# R2020Interface.net
KiCad netlist of a schematic drawn in EAGLE
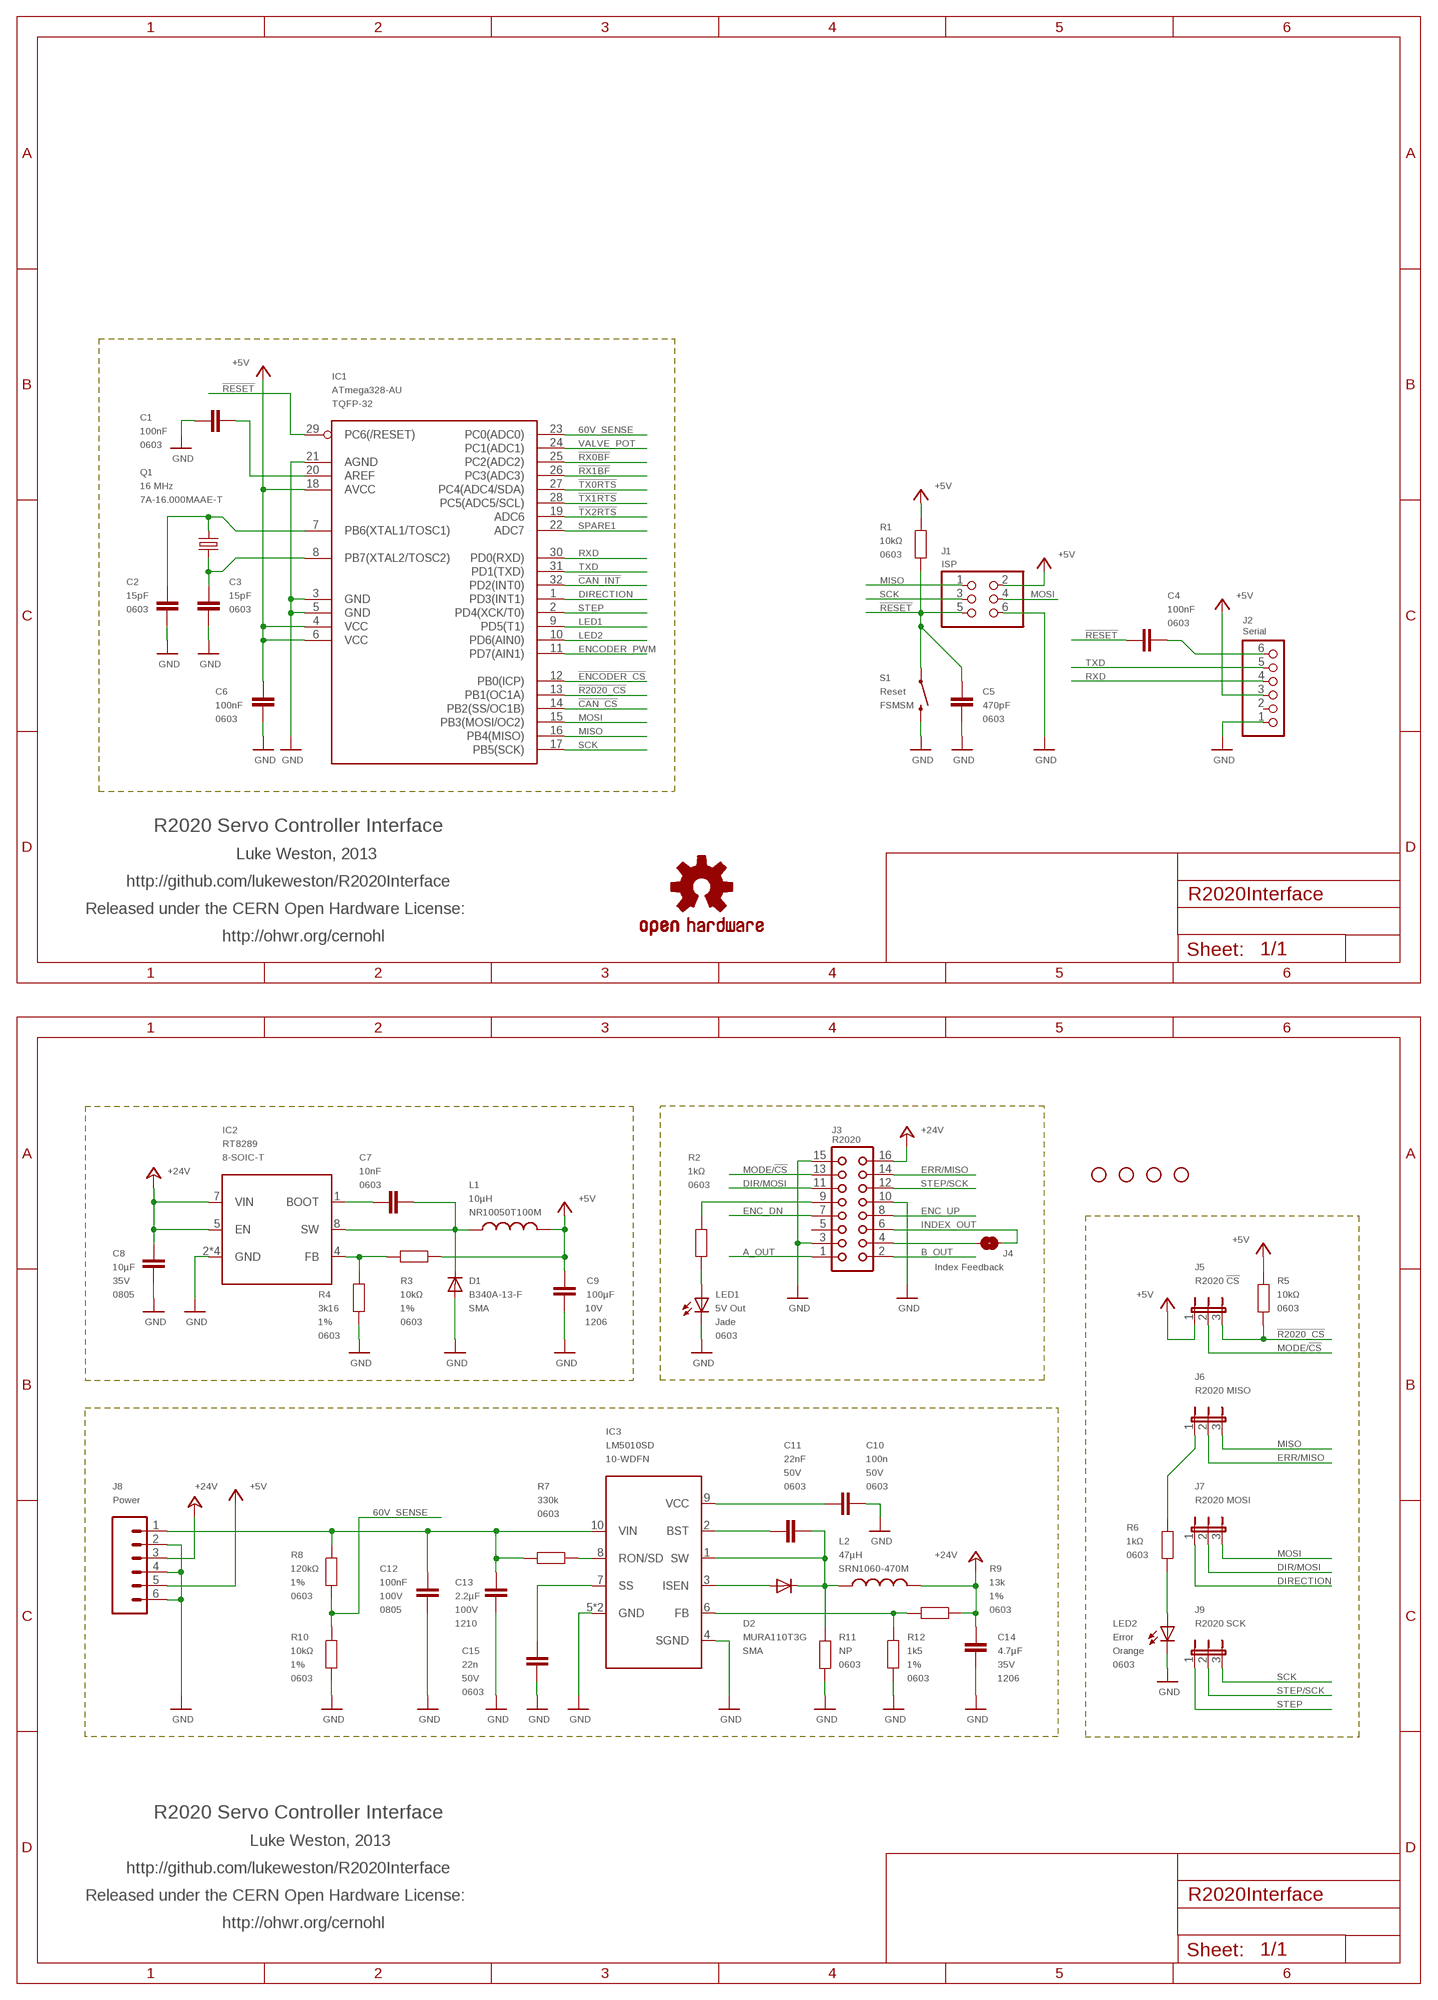
[diagram p0: schematic, sheet 1, part 1 of 2]
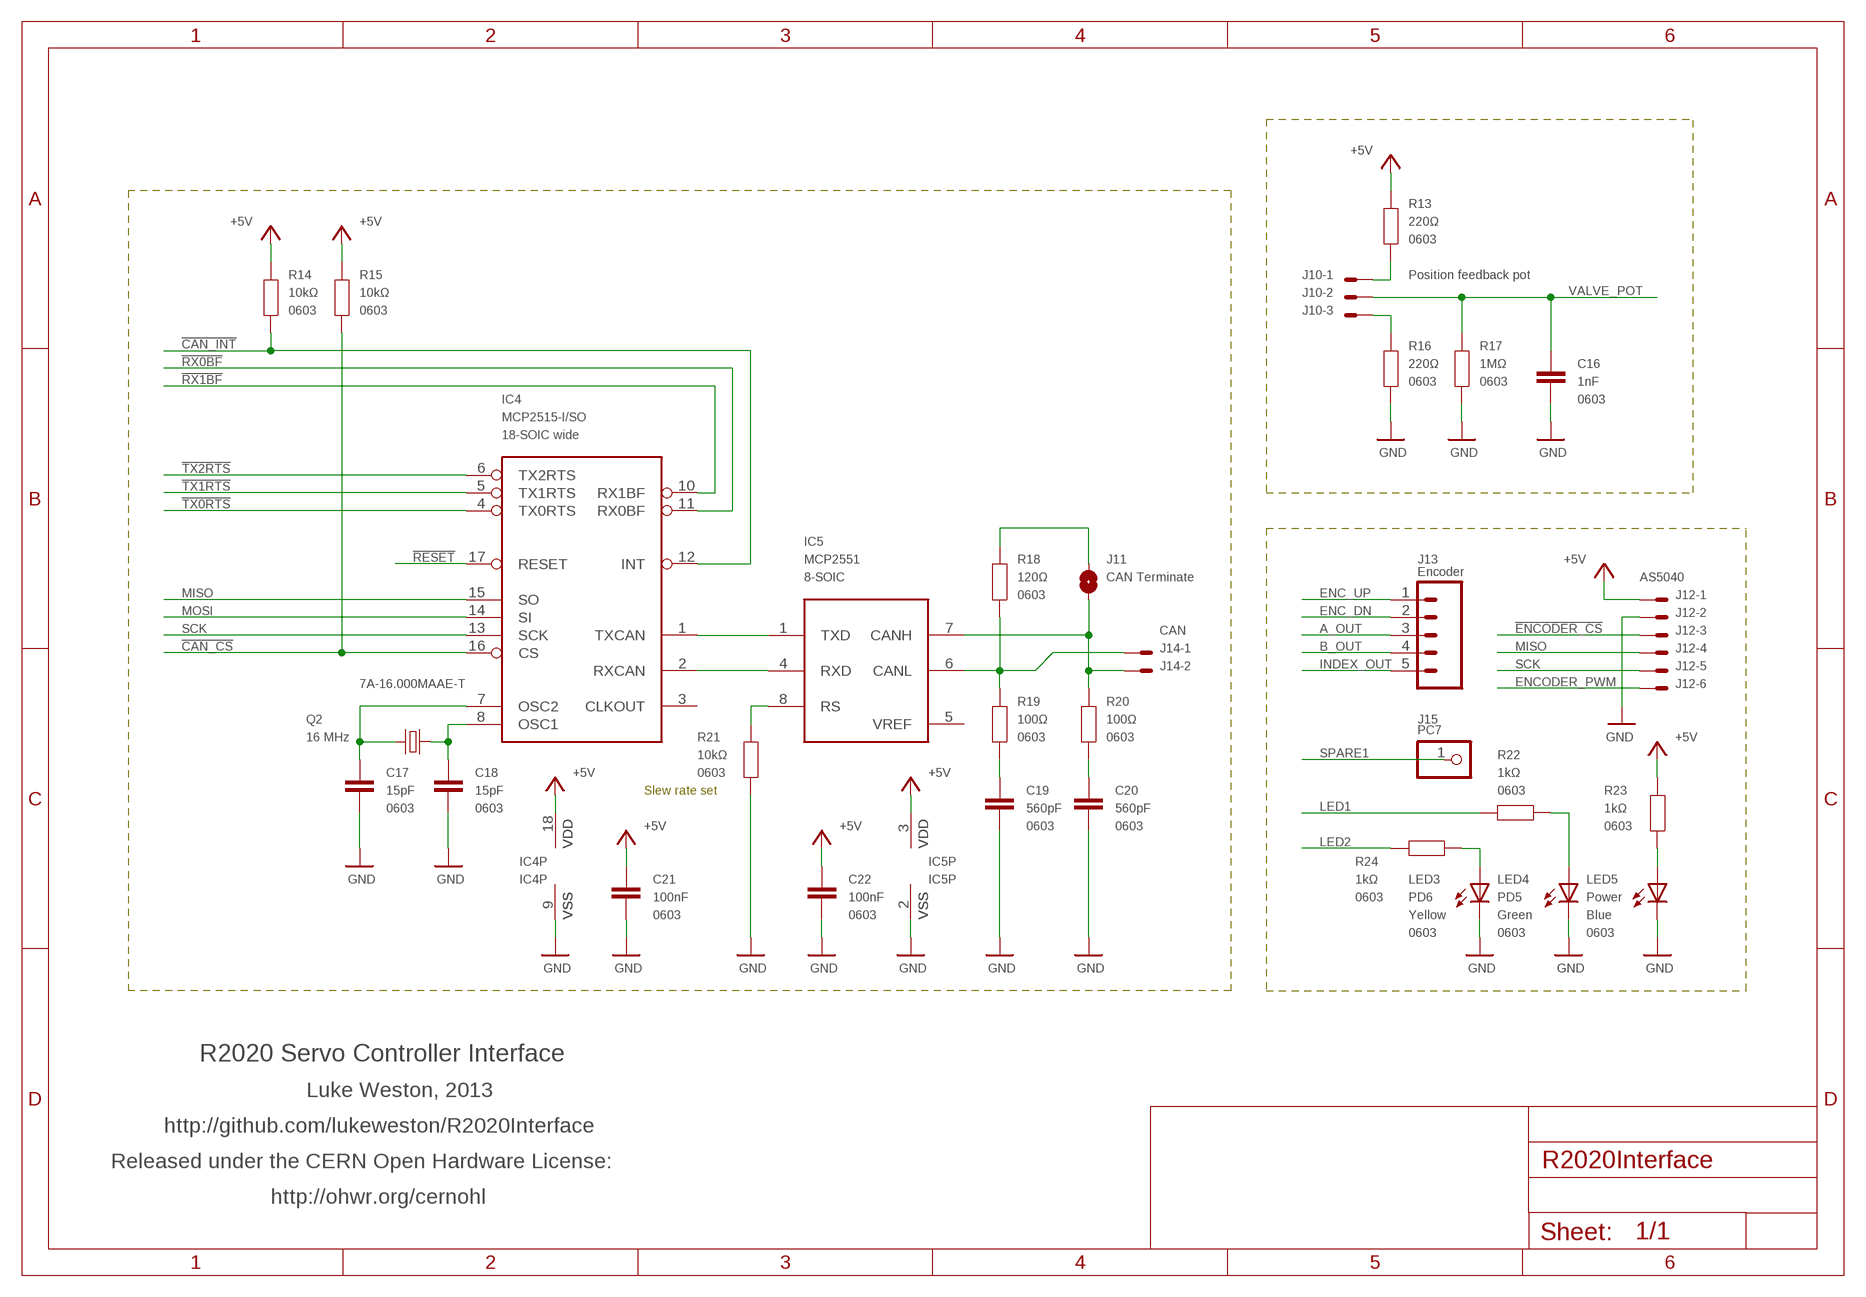
[diagram p1: schematic, sheet 1, part 2 of 2]

(export (version "E")
  (design (tool "Eeschema 10.0.6"))
  (components
    (comp (ref "C1")
      (value "100nF")
      (footprint "eagle-import:0603")
      (fields (field (name "PACKAGE") "0603"))
      (libsource (lib "eagle-import") (part "CAP0603"))
    )
    (comp (ref "C2")
      (value "15pF")
      (footprint "eagle-import:0603")
      (fields (field (name "PACKAGE") "0603"))
      (libsource (lib "eagle-import") (part "CAP0603"))
    )
    (comp (ref "C3")
      (value "15pF")
      (footprint "eagle-import:0603")
      (fields (field (name "PACKAGE") "0603"))
      (libsource (lib "eagle-import") (part "CAP0603"))
    )
    (comp (ref "C4")
      (value "100nF")
      (footprint "eagle-import:0603")
      (fields (field (name "PACKAGE") "0603"))
      (libsource (lib "eagle-import") (part "CAP0603"))
    )
    (comp (ref "C5")
      (value "470pF")
      (footprint "eagle-import:0603")
      (fields (field (name "PACKAGE") "0603"))
      (libsource (lib "eagle-import") (part "CAP0603"))
    )
    (comp (ref "C6")
      (value "100nF")
      (footprint "eagle-import:0603")
      (fields (field (name "PACKAGE") "0603"))
      (libsource (lib "eagle-import") (part "CAP0603"))
    )
    (comp (ref "C7")
      (value "10nF")
      (footprint "eagle-import:0603")
      (fields (field (name "PACKAGE") "0603"))
      (libsource (lib "eagle-import") (part "CAP0603"))
    )
    (comp (ref "C8")
      (value "10µF")
      (footprint "eagle-import:0805")
      (fields (field (name "PACKAGE") "0805") (field (name "VOLTAGE") "35V"))
      (libsource (lib "eagle-import") (part "CAP0805"))
    )
    (comp (ref "C9")
      (value "100µF")
      (footprint "eagle-import:C1206K")
      (fields (field (name "PACKAGE") "1206") (field (name "VOLTAGE") "10V"))
      (libsource (lib "eagle-import") (part "C-EUC1206K"))
    )
    (comp (ref "C10")
      (value "100n")
      (footprint "eagle-import:0603")
      (fields (field (name "PACKAGE") "0603") (field (name "VOLTAGE") "50V"))
      (libsource (lib "eagle-import") (part "CAP0603"))
    )
    (comp (ref "C11")
      (value "22nF")
      (footprint "eagle-import:0603")
      (fields (field (name "PACKAGE") "0603") (field (name "VOLTAGE") "50V"))
      (libsource (lib "eagle-import") (part "CAP0603"))
    )
    (comp (ref "C12")
      (value "100nF")
      (footprint "eagle-import:0805")
      (fields (field (name "PACKAGE") "0805") (field (name "VOLTAGE") "100V"))
      (libsource (lib "eagle-import") (part "CAP0805"))
    )
    (comp (ref "C13")
      (value "2.2µF")
      (footprint "eagle-import:C1210K")
      (fields (field (name "PACKAGE") "1210") (field (name "VOLTAGE") "100V"))
      (libsource (lib "eagle-import") (part "C-EUC1210K"))
    )
    (comp (ref "C14")
      (value "4.7µF")
      (footprint "eagle-import:C1206K")
      (fields (field (name "PACKAGE") "1206") (field (name "VOLTAGE") "35V"))
      (libsource (lib "eagle-import") (part "C-EUC1206K"))
    )
    (comp (ref "C15")
      (value "22n")
      (footprint "eagle-import:0603")
      (fields (field (name "PACKAGE") "0603") (field (name "VOLTAGE") "50V"))
      (libsource (lib "eagle-import") (part "CAP0603"))
    )
    (comp (ref "C16")
      (value "1nF")
      (footprint "eagle-import:0603")
      (fields (field (name "PACKAGE") "0603"))
      (libsource (lib "eagle-import") (part "CAP0603"))
    )
    (comp (ref "C17")
      (value "15pF")
      (footprint "eagle-import:0603")
      (fields (field (name "PACKAGE") "0603"))
      (libsource (lib "eagle-import") (part "CAP0603"))
    )
    (comp (ref "C18")
      (value "15pF")
      (footprint "eagle-import:0603")
      (fields (field (name "PACKAGE") "0603"))
      (libsource (lib "eagle-import") (part "CAP0603"))
    )
    (comp (ref "C19")
      (value "560pF")
      (footprint "eagle-import:0603")
      (fields (field (name "PACKAGE") "0603"))
      (libsource (lib "eagle-import") (part "CAP0603"))
    )
    (comp (ref "C20")
      (value "560pF")
      (footprint "eagle-import:0603")
      (fields (field (name "PACKAGE") "0603"))
      (libsource (lib "eagle-import") (part "CAP0603"))
    )
    (comp (ref "C21")
      (value "100nF")
      (footprint "eagle-import:0603")
      (fields (field (name "PACKAGE") "0603"))
      (libsource (lib "eagle-import") (part "CAP0603"))
    )
    (comp (ref "C22")
      (value "100nF")
      (footprint "eagle-import:0603")
      (fields (field (name "PACKAGE") "0603"))
      (libsource (lib "eagle-import") (part "CAP0603"))
    )
    (comp (ref "D1")
      (value "B340A-13-F")
      (footprint "eagle-import:SMA-DIODE")
      (fields (field (name "PACKAGE") "SMA"))
      (libsource (lib "eagle-import") (part "DIODESMA"))
    )
    (comp (ref "D2")
      (value "MURA110T3G")
      (footprint "eagle-import:SMA-DIODE")
      (fields (field (name "PACKAGE") "SMA"))
      (libsource (lib "eagle-import") (part "DIODESMA"))
    )
    (comp (ref "IC1")
      (value "ATmega328-AU")
      (footprint "eagle-import:TQFP32-08")
      (fields (field (name "PACKAGE") "TQFP-32"))
      (libsource (lib "eagle-import") (part "AVR-MEGA8-AI"))
    )
    (comp (ref "IC2")
      (value "RT8289")
      (footprint "eagle-import:SO08T")
      (fields (field (name "PACKAGE") "8-SOIC-T"))
      (libsource (lib "eagle-import") (part "RT8289"))
    )
    (comp (ref "IC3")
      (value "LM5010SD")
      (footprint "eagle-import:10-WSON")
      (fields (field (name "PACKAGE") "10-WDFN"))
      (libsource (lib "eagle-import") (part "LM5010"))
    )
    (comp (ref "IC4")
      (value "MCP2515-I/SO")
      (footprint "eagle-import:SO-18W")
      (fields (field (name "PACKAGE") "18-SOIC wide"))
      (libsource (lib "eagle-import") (part "MCP2510SO"))
    )
    (comp (ref "IC5")
      (value "MCP2551")
      (footprint "eagle-import:SO-08")
      (fields (field (name "PACKAGE") "8-SOIC"))
      (libsource (lib "eagle-import") (part "MCP2551SN"))
    )
    (comp (ref "J1")
      (value "ISP")
      (footprint "eagle-import:2X03")
      (libsource (lib "eagle-import") (part "PINHD-2X3"))
    )
    (comp (ref "J2")
      (value "Serial")
      (footprint "eagle-import:1X06")
      (libsource (lib "eagle-import") (part "PINHD-1X6"))
    )
    (comp (ref "J3")
      (value "R2020")
      (footprint "eagle-import:CON16")
      (fields (field (name "OC_FARNELL") "unknown") (field (name "OC_NEWARK") "unknown"))
      (libsource (lib "eagle-import") (part "CON16"))
    )
    (comp (ref "J4")
      (value "Index Feedback")
      (footprint "eagle-import:SJ")
      (libsource (lib "eagle-import") (part "SJ"))
    )
    (comp (ref "J5")
      (value "R2020 !CS")
      (footprint "eagle-import:JP2")
      (libsource (lib "eagle-import") (part "JP2E"))
    )
    (comp (ref "J6")
      (value "R2020 MISO")
      (footprint "eagle-import:JP2")
      (libsource (lib "eagle-import") (part "JP2E"))
    )
    (comp (ref "J7")
      (value "R2020 MOSI")
      (footprint "eagle-import:JP2")
      (libsource (lib "eagle-import") (part "JP2E"))
    )
    (comp (ref "J8")
      (value "Power")
      (footprint "eagle-import:TERMINALBLOCK_3.5MM_6")
      (libsource (lib "eagle-import") (part "M06"))
    )
    (comp (ref "J9")
      (value "R2020 SCK")
      (footprint "eagle-import:JP2")
      (libsource (lib "eagle-import") (part "JP2E"))
    )
    (comp (ref "J10")
      (value "Position feedback pot")
      (footprint "eagle-import:7395-03")
      (libsource (lib "eagle-import") (part "22-?-0305-7038"))
    )
    (comp (ref "J11")
      (value "CAN Terminate")
      (footprint "eagle-import:SJ")
      (libsource (lib "eagle-import") (part "SJ"))
    )
    (comp (ref "J12")
      (value "AS5040")
      (footprint "eagle-import:7395-06")
      (fields (field (name "OC_FARNELL") "unknown") (field (name "OC_NEWARK") "unknown"))
      (libsource (lib "eagle-import") (part "22-?-0605-7068"))
    )
    (comp (ref "J13")
      (value "Encoder")
      (footprint "eagle-import:1X05")
      (libsource (lib "eagle-import") (part "M05PTH"))
    )
    (comp (ref "J14")
      (value "CAN")
      (footprint "eagle-import:7395-02")
      (libsource (lib "eagle-import") (part "22-?-0205-7028"))
    )
    (comp (ref "J15")
      (value "PC7")
      (footprint "eagle-import:1X01")
      (libsource (lib "eagle-import") (part "PINHD-1X1"))
    )
    (comp (ref "JP1")
      (value "STAND-OFF")
      (footprint "eagle-import:STAND-OFF")
      (libsource (lib "eagle-import") (part "STAND-OFF"))
    )
    (comp (ref "JP2")
      (value "STAND-OFF")
      (footprint "eagle-import:STAND-OFF")
      (libsource (lib "eagle-import") (part "STAND-OFF"))
    )
    (comp (ref "JP3")
      (value "STAND-OFF")
      (footprint "eagle-import:STAND-OFF")
      (libsource (lib "eagle-import") (part "STAND-OFF"))
    )
    (comp (ref "JP4")
      (value "STAND-OFF")
      (footprint "eagle-import:STAND-OFF")
      (libsource (lib "eagle-import") (part "STAND-OFF"))
    )
    (comp (ref "L1")
      (value "10µH")
      (footprint "eagle-import:NR10050")
      (fields (field (name "ID") "NR10050T100M"))
      (libsource (lib "eagle-import") (part "NR10050"))
    )
    (comp (ref "L2")
      (value "47µH")
      (footprint "eagle-import:SRN1060")
      (fields (field (name "ID") "SRN1060-470M"))
      (libsource (lib "eagle-import") (part "SRN1060"))
    )
    (comp (ref "LED1")
      (value "5V Out")
      (footprint "eagle-import:LED-0603")
      (fields (field (name "COLOR") "Jade") (field (name "PACKAGE") "0603"))
      (libsource (lib "eagle-import") (part "LED0603"))
    )
    (comp (ref "LED2")
      (value "Error")
      (footprint "eagle-import:LED-0603")
      (fields (field (name "COLOR") "Orange") (field (name "PACKAGE") "0603"))
      (libsource (lib "eagle-import") (part "LED0603"))
    )
    (comp (ref "LED3")
      (value "PD6")
      (footprint "eagle-import:LED-0603")
      (fields (field (name "COLOR") "Yellow") (field (name "PACKAGE") "0603"))
      (libsource (lib "eagle-import") (part "LED0603"))
    )
    (comp (ref "LED4")
      (value "PD5")
      (footprint "eagle-import:LED-0603")
      (fields (field (name "COLOR") "Green") (field (name "PACKAGE") "0603"))
      (libsource (lib "eagle-import") (part "LED0603"))
    )
    (comp (ref "LED5")
      (value "Power")
      (footprint "eagle-import:LED-0603")
      (fields (field (name "COLOR") "Blue") (field (name "PACKAGE") "0603"))
      (libsource (lib "eagle-import") (part "LED0603"))
    )
    (comp (ref "Q1")
      (value "16 MHz")
      (footprint "eagle-import:CRYSTAL-3.2X5MM")
      (fields (field (name "ID") "7A-16.000MAAE-T"))
      (libsource (lib "eagle-import") (part "CRYSTAL-2LEAD3.2X5"))
    )
    (comp (ref "Q2")
      (value "16 MHz")
      (footprint "eagle-import:CRYSTAL-3.2X5MM")
      (fields (field (name "ID") "7A-16.000MAAE-T"))
      (libsource (lib "eagle-import") (part "CRYSTAL-2LEAD3.2X5"))
    )
    (comp (ref "R1")
      (value "10kΩ")
      (footprint "eagle-import:0603")
      (fields (field (name "PACKAGE") "0603"))
      (libsource (lib "eagle-import") (part "RESISTOR0603"))
    )
    (comp (ref "R2")
      (value "1kΩ")
      (footprint "eagle-import:0603")
      (fields (field (name "PACKAGE") "0603"))
      (libsource (lib "eagle-import") (part "RESISTOR0603"))
    )
    (comp (ref "R3")
      (value "10kΩ")
      (footprint "eagle-import:0603")
      (fields (field (name "PACKAGE") "0603") (field (name "TOLERANCE") "1%"))
      (libsource (lib "eagle-import") (part "RESISTOR0603"))
    )
    (comp (ref "R4")
      (value "3k16")
      (footprint "eagle-import:0603")
      (fields (field (name "PACKAGE") "0603") (field (name "TOLERANCE") "1%"))
      (libsource (lib "eagle-import") (part "RESISTOR0603"))
    )
    (comp (ref "R5")
      (value "10kΩ")
      (footprint "eagle-import:0603")
      (fields (field (name "PACKAGE") "0603"))
      (libsource (lib "eagle-import") (part "RESISTOR0603"))
    )
    (comp (ref "R6")
      (value "1kΩ")
      (footprint "eagle-import:0603")
      (fields (field (name "PACKAGE") "0603"))
      (libsource (lib "eagle-import") (part "RESISTOR0603"))
    )
    (comp (ref "R7")
      (value "330k")
      (footprint "eagle-import:0603")
      (fields (field (name "PACKAGE") "0603"))
      (libsource (lib "eagle-import") (part "RESISTOR0603"))
    )
    (comp (ref "R8")
      (value "120kΩ")
      (footprint "eagle-import:0603")
      (fields (field (name "PACKAGE") "0603") (field (name "TOLERANCE") "1%"))
      (libsource (lib "eagle-import") (part "RESISTOR0603"))
    )
    (comp (ref "R9")
      (value "13k")
      (footprint "eagle-import:0603")
      (fields (field (name "PACKAGE") "0603") (field (name "TOLERANCE") "1%"))
      (libsource (lib "eagle-import") (part "RESISTOR0603"))
    )
    (comp (ref "R10")
      (value "10kΩ")
      (footprint "eagle-import:0603")
      (fields (field (name "PACKAGE") "0603") (field (name "TOLERANCE") "1%"))
      (libsource (lib "eagle-import") (part "RESISTOR0603"))
    )
    (comp (ref "R11")
      (value "NP")
      (footprint "eagle-import:0603")
      (fields (field (name "PACKAGE") "0603"))
      (libsource (lib "eagle-import") (part "RESISTOR0603"))
    )
    (comp (ref "R12")
      (value "1k5")
      (footprint "eagle-import:0603")
      (fields (field (name "PACKAGE") "0603") (field (name "TOLERANCE") "1%"))
      (libsource (lib "eagle-import") (part "RESISTOR0603"))
    )
    (comp (ref "R13")
      (value "220Ω")
      (footprint "eagle-import:0603")
      (fields (field (name "PACKAGE") "0603"))
      (libsource (lib "eagle-import") (part "RESISTOR0603"))
    )
    (comp (ref "R14")
      (value "10kΩ")
      (footprint "eagle-import:0603")
      (fields (field (name "PACKAGE") "0603"))
      (libsource (lib "eagle-import") (part "RESISTOR0603"))
    )
    (comp (ref "R15")
      (value "10kΩ")
      (footprint "eagle-import:0603")
      (fields (field (name "PACKAGE") "0603"))
      (libsource (lib "eagle-import") (part "RESISTOR0603"))
    )
    (comp (ref "R16")
      (value "220Ω")
      (footprint "eagle-import:0603")
      (fields (field (name "PACKAGE") "0603"))
      (libsource (lib "eagle-import") (part "RESISTOR0603"))
    )
    (comp (ref "R17")
      (value "1MΩ")
      (footprint "eagle-import:0603")
      (fields (field (name "PACKAGE") "0603"))
      (libsource (lib "eagle-import") (part "RESISTOR0603"))
    )
    (comp (ref "R18")
      (value "120Ω")
      (footprint "eagle-import:0603")
      (fields (field (name "PACKAGE") "0603"))
      (libsource (lib "eagle-import") (part "RESISTOR0603"))
    )
    (comp (ref "R19")
      (value "100Ω")
      (footprint "eagle-import:0603")
      (fields (field (name "PACKAGE") "0603"))
      (libsource (lib "eagle-import") (part "RESISTOR0603"))
    )
    (comp (ref "R20")
      (value "100Ω")
      (footprint "eagle-import:0603")
      (fields (field (name "PACKAGE") "0603"))
      (libsource (lib "eagle-import") (part "RESISTOR0603"))
    )
    (comp (ref "R21")
      (value "10kΩ")
      (footprint "eagle-import:0603")
      (fields (field (name "PACKAGE") "0603"))
      (libsource (lib "eagle-import") (part "RESISTOR0603"))
    )
    (comp (ref "R22")
      (value "1kΩ")
      (footprint "eagle-import:0603")
      (fields (field (name "PACKAGE") "0603"))
      (libsource (lib "eagle-import") (part "RESISTOR0603"))
    )
    (comp (ref "R23")
      (value "1kΩ")
      (footprint "eagle-import:0603")
      (fields (field (name "PACKAGE") "0603"))
      (libsource (lib "eagle-import") (part "RESISTOR0603"))
    )
    (comp (ref "R24")
      (value "1kΩ")
      (footprint "eagle-import:0603")
      (fields (field (name "PACKAGE") "0603"))
      (libsource (lib "eagle-import") (part "RESISTOR0603"))
    )
    (comp (ref "S1")
      (value "Reset")
      (footprint "eagle-import:FSMSM")
      (fields (field (name "PACKAGE") "FSMSM"))
      (libsource (lib "eagle-import") (part "FSMSM"))
    )
    (comp (ref "SY1")
      (value "OSHW-LOGOS")
      (footprint "eagle-import:OSHW-LOGO-S")
      (libsource (lib "eagle-import") (part "OSHW-LOGOS"))
    )
  )
  (nets
    (net (code "1") (name "+5V") (class "Default")
      (node (ref "C21") (pin "2") (pinfunction "2_2") (pintype "passive"))
      (node (ref "C22") (pin "2") (pinfunction "2_2") (pintype "passive"))
      (node (ref "C6") (pin "1") (pinfunction "1_1") (pintype "passive"))
      (node (ref "C9") (pin "1") (pinfunction "1_1") (pintype "passive"))
      (node (ref "IC1") (pin "18") (pinfunction "AVCC_18") (pintype "bidirectional"))
      (node (ref "IC1") (pin "4") (pinfunction "VCC_4") (pintype "bidirectional"))
      (node (ref "IC1") (pin "6") (pinfunction "VCC_6") (pintype "bidirectional"))
      (node (ref "IC4") (pin "18") (pinfunction "VDD_18") (pintype "power_in"))
      (node (ref "IC5") (pin "3") (pinfunction "VDD_3") (pintype "power_in"))
      (node (ref "J1") (pin "2") (pinfunction "2_2") (pintype "passive"))
      (node (ref "J12") (pin "1") (pinfunction "S_1") (pintype "passive"))
      (node (ref "J2") (pin "3") (pinfunction "3_3") (pintype "passive"))
      (node (ref "J5") (pin "1") (pinfunction "1_1") (pintype "passive"))
      (node (ref "J8") (pin "5") (pinfunction "5_5") (pintype "passive"))
      (node (ref "L1") (pin "2") (pinfunction "2_2") (pintype "bidirectional"))
      (node (ref "R1") (pin "2") (pinfunction "2_2") (pintype "passive"))
      (node (ref "R13") (pin "1") (pinfunction "1_1") (pintype "passive"))
      (node (ref "R14") (pin "1") (pinfunction "1_1") (pintype "passive"))
      (node (ref "R15") (pin "1") (pinfunction "1_1") (pintype "passive"))
      (node (ref "R23") (pin "1") (pinfunction "1_1") (pintype "passive"))
      (node (ref "R3") (pin "1") (pinfunction "1_1") (pintype "passive"))
      (node (ref "R5") (pin "1") (pinfunction "1_1") (pintype "passive"))
    )
    (net (code "2") (name "+24V") (class "Default")
      (node (ref "C14") (pin "1") (pinfunction "1_1") (pintype "passive"))
      (node (ref "C8") (pin "2") (pinfunction "2_2") (pintype "passive"))
      (node (ref "IC2") (pin "5") (pinfunction "EN_5") (pintype "bidirectional"))
      (node (ref "IC2") (pin "7") (pinfunction "VIN_7") (pintype "bidirectional"))
      (node (ref "J3") (pin "16") (pinfunction "16_16") (pintype "passive"))
      (node (ref "J8") (pin "3") (pinfunction "3_3") (pintype "passive"))
      (node (ref "L2") (pin "2") (pinfunction "2_2") (pintype "bidirectional"))
      (node (ref "R9") (pin "1") (pinfunction "1_1") (pintype "passive"))
    )
    (net (code "3") (name "/60V_SENSE") (class "Default")
      (node (ref "IC1") (pin "23") (pinfunction "PC0(ADC0)_23") (pintype "bidirectional"))
      (node (ref "R10") (pin "2") (pinfunction "2_2") (pintype "passive"))
      (node (ref "R8") (pin "1") (pinfunction "1_1") (pintype "passive"))
    )
    (net (code "4") (name "/A_OUT") (class "Default")
      (node (ref "J13") (pin "3") (pinfunction "3_3") (pintype "passive"))
      (node (ref "J3") (pin "1") (pinfunction "1_1") (pintype "passive"))
    )
    (net (code "5") (name "/B_OUT") (class "Default")
      (node (ref "J13") (pin "4") (pinfunction "4_4") (pintype "passive"))
      (node (ref "J3") (pin "2") (pinfunction "2_2") (pintype "passive"))
    )
    (net (code "6") (name "/DIRECTION") (class "Default")
      (node (ref "IC1") (pin "1") (pinfunction "PD3(INT1)_1") (pintype "bidirectional"))
      (node (ref "J7") (pin "1") (pinfunction "1_1") (pintype "passive"))
    )
    (net (code "7") (name "/DIR{slash}MOSI") (class "Default")
      (node (ref "J3") (pin "11") (pinfunction "11_11") (pintype "passive"))
      (node (ref "J7") (pin "2") (pinfunction "2_2") (pintype "passive"))
    )
    (net (code "8") (name "/ENCODER_PWM") (class "Default")
      (node (ref "IC1") (pin "11") (pinfunction "PD7(AIN1)_11") (pintype "bidirectional"))
      (node (ref "J12") (pin "6") (pinfunction "S_6") (pintype "passive"))
    )
    (net (code "9") (name "/ENC_DN") (class "Default")
      (node (ref "J13") (pin "2") (pinfunction "2_2") (pintype "passive"))
      (node (ref "J3") (pin "7") (pinfunction "7_7") (pintype "passive"))
    )
    (net (code "10") (name "/ENC_UP") (class "Default")
      (node (ref "J13") (pin "1") (pinfunction "1_1") (pintype "passive"))
      (node (ref "J3") (pin "8") (pinfunction "8_8") (pintype "passive"))
    )
    (net (code "11") (name "/ERR{slash}MISO") (class "Default")
      (node (ref "J3") (pin "14") (pinfunction "14_14") (pintype "passive"))
      (node (ref "J6") (pin "2") (pinfunction "2_2") (pintype "passive"))
    )
    (net (code "12") (name "/INDEX_OUT") (class "Default")
      (node (ref "J13") (pin "5") (pinfunction "5_5") (pintype "passive"))
      (node (ref "J3") (pin "6") (pinfunction "6_6") (pintype "passive"))
      (node (ref "J4") (pin "1") (pinfunction "1_1") (pintype "passive"))
    )
    (net (code "13") (name "/LED1") (class "Default")
      (node (ref "IC1") (pin "9") (pinfunction "PD5(T1)_9") (pintype "bidirectional"))
      (node (ref "R22") (pin "2") (pinfunction "2_2") (pintype "passive"))
    )
    (net (code "14") (name "/LED2") (class "Default")
      (node (ref "IC1") (pin "10") (pinfunction "PD6(AIN0)_10") (pintype "bidirectional"))
      (node (ref "R24") (pin "2") (pinfunction "2_2") (pintype "passive"))
    )
    (net (code "15") (name "/MISO") (class "Default")
      (node (ref "IC1") (pin "16") (pinfunction "PB4(MISO)_16") (pintype "bidirectional"))
      (node (ref "IC4") (pin "15") (pinfunction "SO_15") (pintype "output"))
      (node (ref "J1") (pin "1") (pinfunction "1_1") (pintype "passive"))
      (node (ref "J12") (pin "4") (pinfunction "S_4") (pintype "passive"))
      (node (ref "J6") (pin "3") (pinfunction "3_3") (pintype "passive"))
    )
    (net (code "16") (name "/MODE{slash}~{CS}") (class "Default")
      (node (ref "J3") (pin "13") (pinfunction "13_13") (pintype "passive"))
      (node (ref "J5") (pin "2") (pinfunction "2_2") (pintype "passive"))
    )
    (net (code "17") (name "/MOSI") (class "Default")
      (node (ref "IC1") (pin "15") (pinfunction "PB3(MOSI/OC2)_15") (pintype "bidirectional"))
      (node (ref "IC4") (pin "14") (pinfunction "SI_14") (pintype "input"))
      (node (ref "J1") (pin "4") (pinfunction "4_4") (pintype "passive"))
      (node (ref "J7") (pin "3") (pinfunction "3_3") (pintype "passive"))
    )
    (net (code "18") (name "/RXD") (class "Default")
      (node (ref "IC1") (pin "30") (pinfunction "PD0(RXD)_30") (pintype "bidirectional"))
      (node (ref "J2") (pin "4") (pinfunction "4_4") (pintype "passive"))
    )
    (net (code "19") (name "/SCK") (class "Default")
      (node (ref "IC1") (pin "17") (pinfunction "PB5(SCK)_17") (pintype "bidirectional"))
      (node (ref "IC4") (pin "13") (pinfunction "SCK_13") (pintype "input"))
      (node (ref "J1") (pin "3") (pinfunction "3_3") (pintype "passive"))
      (node (ref "J12") (pin "5") (pinfunction "S_5") (pintype "passive"))
      (node (ref "J9") (pin "3") (pinfunction "3_3") (pintype "passive"))
    )
    (net (code "20") (name "/SPARE1") (class "Default")
      (node (ref "IC1") (pin "22") (pinfunction "ADC7_22") (pintype "bidirectional"))
      (node (ref "J15") (pin "1") (pinfunction "1_1") (pintype "passive"))
    )
    (net (code "21") (name "/STEP") (class "Default")
      (node (ref "IC1") (pin "2") (pinfunction "PD4(XCK/T0)_2") (pintype "bidirectional"))
      (node (ref "J9") (pin "1") (pinfunction "1_1") (pintype "passive"))
    )
    (net (code "22") (name "/STEP{slash}SCK") (class "Default")
      (node (ref "J3") (pin "12") (pinfunction "12_12") (pintype "passive"))
      (node (ref "J9") (pin "2") (pinfunction "2_2") (pintype "passive"))
    )
    (net (code "23") (name "/TXD") (class "Default")
      (node (ref "IC1") (pin "31") (pinfunction "PD1(TXD)_31") (pintype "bidirectional"))
      (node (ref "J2") (pin "5") (pinfunction "5_5") (pintype "passive"))
    )
    (net (code "24") (name "/VALVE_POT") (class "Default")
      (node (ref "C16") (pin "2") (pinfunction "2_2") (pintype "passive"))
      (node (ref "IC1") (pin "24") (pinfunction "PC1(ADC1)_24") (pintype "bidirectional"))
      (node (ref "J10") (pin "2") (pinfunction "S_2") (pintype "passive"))
      (node (ref "R17") (pin "1") (pinfunction "1_1") (pintype "passive"))
    )
    (net (code "25") (name "/VREF") (class "Default")
      (node (ref "IC5") (pin "5") (pinfunction "VREF_5") (pintype "power_in"))
    )
    (net (code "26") (name "/~{CAN_CS}") (class "Default")
      (node (ref "IC1") (pin "14") (pinfunction "PB2(SS/OC1B)_14") (pintype "bidirectional"))
      (node (ref "IC4") (pin "16") (pinfunction "CS_16") (pintype "input"))
      (node (ref "R15") (pin "2") (pinfunction "2_2") (pintype "passive"))
    )
    (net (code "27") (name "/~{CAN_INT}") (class "Default")
      (node (ref "IC1") (pin "32") (pinfunction "PD2(INT0)_32") (pintype "bidirectional"))
      (node (ref "IC4") (pin "12") (pinfunction "INT_12") (pintype "output"))
      (node (ref "R14") (pin "2") (pinfunction "2_2") (pintype "passive"))
    )
    (net (code "28") (name "/~{ENCODER_CS}") (class "Default")
      (node (ref "IC1") (pin "12") (pinfunction "PB0(ICP)_12") (pintype "bidirectional"))
      (node (ref "J12") (pin "3") (pinfunction "S_3") (pintype "passive"))
    )
    (net (code "29") (name "/~{R2020_CS}") (class "Default")
      (node (ref "IC1") (pin "13") (pinfunction "PB1(OC1A)_13") (pintype "bidirectional"))
      (node (ref "J5") (pin "3") (pinfunction "3_3") (pintype "passive"))
      (node (ref "R5") (pin "2") (pinfunction "2_2") (pintype "passive"))
    )
    (net (code "30") (name "/~{RESET}") (class "Default")
      (node (ref "C4") (pin "1") (pinfunction "1_1") (pintype "passive"))
      (node (ref "C5") (pin "2") (pinfunction "2_2") (pintype "passive"))
      (node (ref "IC1") (pin "29") (pinfunction "PC6(/RESET)_29") (pintype "bidirectional"))
      (node (ref "IC4") (pin "17") (pinfunction "RESET_17") (pintype "input"))
      (node (ref "J1") (pin "5") (pinfunction "5_5") (pintype "passive"))
      (node (ref "R1") (pin "1") (pinfunction "1_1") (pintype "passive"))
      (node (ref "S1") (pin "1") (pinfunction "1_1") (pintype "passive"))
    )
    (net (code "31") (name "/~{RX0BF}") (class "Default")
      (node (ref "IC1") (pin "25") (pinfunction "PC2(ADC2)_25") (pintype "bidirectional"))
      (node (ref "IC4") (pin "11") (pinfunction "RX0BF_11") (pintype "output"))
    )
    (net (code "32") (name "/~{RX1BF}") (class "Default")
      (node (ref "IC1") (pin "26") (pinfunction "PC3(ADC3)_26") (pintype "bidirectional"))
      (node (ref "IC4") (pin "10") (pinfunction "RX1BF_10") (pintype "output"))
    )
    (net (code "33") (name "/~{TX0RTS}") (class "Default")
      (node (ref "IC1") (pin "27") (pinfunction "PC4(ADC4/SDA)_27") (pintype "bidirectional"))
      (node (ref "IC4") (pin "4") (pinfunction "TX0RTS_4") (pintype "input"))
    )
    (net (code "34") (name "/~{TX1RTS}") (class "Default")
      (node (ref "IC1") (pin "28") (pinfunction "PC5(ADC5/SCL)_28") (pintype "bidirectional"))
      (node (ref "IC4") (pin "5") (pinfunction "TX1RTS_5") (pintype "input"))
    )
    (net (code "35") (name "/~{TX2RTS}") (class "Default")
      (node (ref "IC1") (pin "19") (pinfunction "ADC6_19") (pintype "bidirectional"))
      (node (ref "IC4") (pin "6") (pinfunction "TX2RTS_6") (pintype "input"))
    )
    (net (code "36") (name "GND") (class "Default")
      (node (ref "C1") (pin "2") (pinfunction "2_2") (pintype "passive"))
      (node (ref "C10") (pin "1") (pinfunction "1_1") (pintype "passive"))
      (node (ref "C12") (pin "1") (pinfunction "1_1") (pintype "passive"))
      (node (ref "C13") (pin "2") (pinfunction "2_2") (pintype "passive"))
      (node (ref "C14") (pin "2") (pinfunction "2_2") (pintype "passive"))
      (node (ref "C15") (pin "1") (pinfunction "1_1") (pintype "passive"))
      (node (ref "C16") (pin "1") (pinfunction "1_1") (pintype "passive"))
      (node (ref "C17") (pin "1") (pinfunction "1_1") (pintype "passive"))
      (node (ref "C18") (pin "1") (pinfunction "1_1") (pintype "passive"))
      (node (ref "C19") (pin "1") (pinfunction "1_1") (pintype "passive"))
      (node (ref "C2") (pin "1") (pinfunction "1_1") (pintype "passive"))
      (node (ref "C20") (pin "1") (pinfunction "1_1") (pintype "passive"))
      (node (ref "C21") (pin "1") (pinfunction "1_1") (pintype "passive"))
      (node (ref "C22") (pin "1") (pinfunction "1_1") (pintype "passive"))
      (node (ref "C3") (pin "1") (pinfunction "1_1") (pintype "passive"))
      (node (ref "C5") (pin "1") (pinfunction "1_1") (pintype "passive"))
      (node (ref "C6") (pin "2") (pinfunction "2_2") (pintype "passive"))
      (node (ref "C8") (pin "1") (pinfunction "1_1") (pintype "passive"))
      (node (ref "C9") (pin "2") (pinfunction "2_2") (pintype "passive"))
      (node (ref "D1") (pin "A") (pinfunction "A_A") (pintype "passive"))
      (node (ref "IC1") (pin "21") (pinfunction "AGND_21") (pintype "bidirectional"))
      (node (ref "IC1") (pin "3") (pinfunction "GND_3") (pintype "bidirectional"))
      (node (ref "IC1") (pin "5") (pinfunction "GND_5") (pintype "bidirectional"))
      (node (ref "IC2") (pin "2") (pinfunction "GND_2") (pintype "bidirectional"))
      (node (ref "IC2") (pin "3") (pinfunction "GND_3") (pintype "bidirectional"))
      (node (ref "IC2") (pin "6") (pinfunction "GND_6") (pintype "bidirectional"))
      (node (ref "IC2") (pin "PAD") (pinfunction "GND_PAD") (pintype "bidirectional"))
      (node (ref "IC3") (pin "4") (pinfunction "SGND_4") (pintype "bidirectional"))
      (node (ref "IC3") (pin "5") (pinfunction "GND_5") (pintype "bidirectional"))
      (node (ref "IC3") (pin "PAD") (pinfunction "GND_PAD") (pintype "bidirectional"))
      (node (ref "IC4") (pin "9") (pinfunction "VSS_9") (pintype "power_in"))
      (node (ref "IC5") (pin "2") (pinfunction "VSS_2") (pintype "power_in"))
      (node (ref "J1") (pin "6") (pinfunction "6_6") (pintype "passive"))
      (node (ref "J12") (pin "2") (pinfunction "S_2") (pintype "passive"))
      (node (ref "J2") (pin "1") (pinfunction "1_1") (pintype "passive"))
      (node (ref "J3") (pin "10") (pinfunction "10_10") (pintype "passive"))
      (node (ref "J3") (pin "15") (pinfunction "15_15") (pintype "passive"))
      (node (ref "J3") (pin "3") (pinfunction "3_3") (pintype "passive"))
      (node (ref "J8") (pin "2") (pinfunction "2_2") (pintype "passive"))
      (node (ref "J8") (pin "4") (pinfunction "4_4") (pintype "passive"))
      (node (ref "J8") (pin "6") (pinfunction "6_6") (pintype "passive"))
      (node (ref "LED1") (pin "C") (pinfunction "C_C") (pintype "passive"))
      (node (ref "LED2") (pin "C") (pinfunction "C_C") (pintype "passive"))
      (node (ref "LED3") (pin "C") (pinfunction "C_C") (pintype "passive"))
      (node (ref "LED4") (pin "C") (pinfunction "C_C") (pintype "passive"))
      (node (ref "LED5") (pin "C") (pinfunction "C_C") (pintype "passive"))
      (node (ref "R10") (pin "1") (pinfunction "1_1") (pintype "passive"))
      (node (ref "R11") (pin "2") (pinfunction "2_2") (pintype "passive"))
      (node (ref "R12") (pin "1") (pinfunction "1_1") (pintype "passive"))
      (node (ref "R16") (pin "2") (pinfunction "2_2") (pintype "passive"))
      (node (ref "R17") (pin "2") (pinfunction "2_2") (pintype "passive"))
      (node (ref "R21") (pin "2") (pinfunction "2_2") (pintype "passive"))
      (node (ref "R4") (pin "1") (pinfunction "1_1") (pintype "passive"))
      (node (ref "S1") (pin "2") (pinfunction "2_2") (pintype "passive"))
    )
    (net (code "37") (name "Net-(C4-Pad2)") (class "Default")
      (node (ref "C4") (pin "2") (pinfunction "2_2") (pintype "passive"))
      (node (ref "J2") (pin "6") (pinfunction "6_6") (pintype "passive"))
    )
    (net (code "38") (name "Net-(C19-Pad2)") (class "Default")
      (node (ref "C19") (pin "2") (pinfunction "2_2") (pintype "passive"))
      (node (ref "R19") (pin "2") (pinfunction "2_2") (pintype "passive"))
    )
    (net (code "39") (name "Net-(C20-Pad2)") (class "Default")
      (node (ref "C20") (pin "2") (pinfunction "2_2") (pintype "passive"))
      (node (ref "R20") (pin "2") (pinfunction "2_2") (pintype "passive"))
    )
    (net (code "40") (name "Net-(IC1-AREF)") (class "Default")
      (node (ref "C1") (pin "1") (pinfunction "1_1") (pintype "passive"))
      (node (ref "IC1") (pin "20") (pinfunction "AREF_20") (pintype "bidirectional"))
    )
    (net (code "41") (name "Net-(IC1-PB6(XTAL1{slash}TOSC1))") (class "Default")
      (node (ref "C2") (pin "2") (pinfunction "2_2") (pintype "passive"))
      (node (ref "IC1") (pin "7") (pinfunction "PB6(XTAL1/TOSC1)_7") (pintype "bidirectional"))
      (node (ref "Q1") (pin "1") (pinfunction "1_1") (pintype "bidirectional"))
    )
    (net (code "42") (name "Net-(IC1-PB7(XTAL2{slash}TOSC2))") (class "Default")
      (node (ref "C3") (pin "2") (pinfunction "2_2") (pintype "passive"))
      (node (ref "IC1") (pin "8") (pinfunction "PB7(XTAL2/TOSC2)_8") (pintype "bidirectional"))
      (node (ref "Q1") (pin "2") (pinfunction "2_2") (pintype "bidirectional"))
    )
    (net (code "43") (name "Net-(IC2-BOOT)") (class "Default")
      (node (ref "C7") (pin "2") (pinfunction "2_2") (pintype "passive"))
      (node (ref "IC2") (pin "1") (pinfunction "BOOT_1") (pintype "bidirectional"))
    )
    (net (code "44") (name "Net-(IC2-FB)") (class "Default")
      (node (ref "IC2") (pin "4") (pinfunction "FB_4") (pintype "bidirectional"))
      (node (ref "R3") (pin "2") (pinfunction "2_2") (pintype "passive"))
      (node (ref "R4") (pin "2") (pinfunction "2_2") (pintype "passive"))
    )
    (net (code "45") (name "Net-(IC2-SW)") (class "Default")
      (node (ref "C7") (pin "1") (pinfunction "1_1") (pintype "passive"))
      (node (ref "D1") (pin "C") (pinfunction "C_C") (pintype "passive"))
      (node (ref "IC2") (pin "8") (pinfunction "SW_8") (pintype "bidirectional"))
      (node (ref "L1") (pin "1") (pinfunction "1_1") (pintype "bidirectional"))
    )
    (net (code "46") (name "Net-(IC3-BST)") (class "Default")
      (node (ref "C11") (pin "2") (pinfunction "2_2") (pintype "passive"))
      (node (ref "IC3") (pin "2") (pinfunction "BST_2") (pintype "bidirectional"))
    )
    (net (code "47") (name "Net-(IC3-FB)") (class "Default")
      (node (ref "IC3") (pin "6") (pinfunction "FB_6") (pintype "bidirectional"))
      (node (ref "R12") (pin "2") (pinfunction "2_2") (pintype "passive"))
      (node (ref "R9") (pin "2") (pinfunction "2_2") (pintype "passive"))
    )
    (net (code "48") (name "Net-(IC3-ISEN)") (class "Default")
      (node (ref "D2") (pin "A") (pinfunction "A_A") (pintype "passive"))
      (node (ref "IC3") (pin "3") (pinfunction "ISEN_3") (pintype "bidirectional"))
    )
    (net (code "49") (name "Net-(IC3-RON{slash}SD)") (class "Default")
      (node (ref "IC3") (pin "8") (pinfunction "RON/SD_8") (pintype "bidirectional"))
      (node (ref "R7") (pin "1") (pinfunction "1_1") (pintype "passive"))
    )
    (net (code "50") (name "Net-(IC3-SS)") (class "Default")
      (node (ref "C15") (pin "2") (pinfunction "2_2") (pintype "passive"))
      (node (ref "IC3") (pin "7") (pinfunction "SS_7") (pintype "bidirectional"))
    )
    (net (code "51") (name "Net-(IC3-SW)") (class "Default")
      (node (ref "C11") (pin "1") (pinfunction "1_1") (pintype "passive"))
      (node (ref "D2") (pin "C") (pinfunction "C_C") (pintype "passive"))
      (node (ref "IC3") (pin "1") (pinfunction "SW_1") (pintype "bidirectional"))
      (node (ref "L2") (pin "1") (pinfunction "1_1") (pintype "bidirectional"))
      (node (ref "R11") (pin "1") (pinfunction "1_1") (pintype "passive"))
    )
    (net (code "52") (name "Net-(IC3-VCC)") (class "Default")
      (node (ref "C10") (pin "2") (pinfunction "2_2") (pintype "passive"))
      (node (ref "IC3") (pin "9") (pinfunction "VCC_9") (pintype "bidirectional"))
    )
    (net (code "53") (name "Net-(IC3-VIN)") (class "Default")
      (node (ref "C12") (pin "2") (pinfunction "2_2") (pintype "passive"))
      (node (ref "C13") (pin "1") (pinfunction "1_1") (pintype "passive"))
      (node (ref "IC3") (pin "10") (pinfunction "VIN_10") (pintype "bidirectional"))
      (node (ref "J8") (pin "1") (pinfunction "1_1") (pintype "passive"))
      (node (ref "R7") (pin "2") (pinfunction "2_2") (pintype "passive"))
      (node (ref "R8") (pin "2") (pinfunction "2_2") (pintype "passive"))
    )
    (net (code "54") (name "Net-(IC4A-OSC1)") (class "Default")
      (node (ref "C18") (pin "2") (pinfunction "2_2") (pintype "passive"))
      (node (ref "IC4") (pin "8") (pinfunction "OSC1_8") (pintype "input"))
      (node (ref "Q2") (pin "1") (pinfunction "1_1") (pintype "bidirectional"))
    )
    (net (code "55") (name "Net-(IC4A-OSC2)") (class "Default")
      (node (ref "C17") (pin "2") (pinfunction "2_2") (pintype "passive"))
      (node (ref "IC4") (pin "7") (pinfunction "OSC2_7") (pintype "output"))
      (node (ref "Q2") (pin "2") (pinfunction "2_2") (pintype "bidirectional"))
    )
    (net (code "56") (name "Net-(IC4A-RXCAN)") (class "Default")
      (node (ref "IC4") (pin "2") (pinfunction "RXCAN_2") (pintype "input"))
      (node (ref "IC5") (pin "4") (pinfunction "RXD_4") (pintype "output"))
    )
    (net (code "57") (name "Net-(IC4A-TXCAN)") (class "Default")
      (node (ref "IC4") (pin "1") (pinfunction "TXCAN_1") (pintype "output"))
      (node (ref "IC5") (pin "1") (pinfunction "TXD_1") (pintype "input"))
    )
    (net (code "58") (name "Net-(IC5A-CANH)") (class "Default")
      (node (ref "IC5") (pin "7") (pinfunction "CANH_7") (pintype "bidirectional"))
      (node (ref "J11") (pin "1") (pinfunction "1_1") (pintype "passive"))
      (node (ref "J14") (pin "2") (pinfunction "S_2") (pintype "passive"))
      (node (ref "R20") (pin "1") (pinfunction "1_1") (pintype "passive"))
    )
    (net (code "59") (name "Net-(IC5A-CANL)") (class "Default")
      (node (ref "IC5") (pin "6") (pinfunction "CANL_6") (pintype "bidirectional"))
      (node (ref "J14") (pin "1") (pinfunction "S_1") (pintype "passive"))
      (node (ref "R18") (pin "2") (pinfunction "2_2") (pintype "passive"))
      (node (ref "R19") (pin "1") (pinfunction "1_1") (pintype "passive"))
    )
    (net (code "60") (name "Net-(IC5A-RS)") (class "Default")
      (node (ref "IC5") (pin "8") (pinfunction "RS_8") (pintype "input"))
      (node (ref "R21") (pin "1") (pinfunction "1_1") (pintype "passive"))
    )
    (net (code "61") (name "Net-(J3-Pad4)") (class "Default")
      (node (ref "J3") (pin "4") (pinfunction "4_4") (pintype "passive"))
      (node (ref "J4") (pin "2") (pinfunction "2_2") (pintype "passive"))
    )
    (net (code "62") (name "Net-(J3-Pad9)") (class "Default")
      (node (ref "J3") (pin "9") (pinfunction "9_9") (pintype "passive"))
      (node (ref "R2") (pin "2") (pinfunction "2_2") (pintype "passive"))
    )
    (net (code "63") (name "Net-(J6-Pad1)") (class "Default")
      (node (ref "J6") (pin "1") (pinfunction "1_1") (pintype "passive"))
      (node (ref "R6") (pin "1") (pinfunction "1_1") (pintype "passive"))
    )
    (net (code "64") (name "Net-(J10A-S)") (class "Default")
      (node (ref "J10") (pin "1") (pinfunction "S_1") (pintype "passive"))
      (node (ref "R13") (pin "2") (pinfunction "2_2") (pintype "passive"))
    )
    (net (code "65") (name "Net-(J10C-S)") (class "Default")
      (node (ref "J10") (pin "3") (pinfunction "S_3") (pintype "passive"))
      (node (ref "R16") (pin "1") (pinfunction "1_1") (pintype "passive"))
    )
    (net (code "66") (name "Net-(J11-Pad2)") (class "Default")
      (node (ref "J11") (pin "2") (pinfunction "2_2") (pintype "passive"))
      (node (ref "R18") (pin "1") (pinfunction "1_1") (pintype "passive"))
    )
    (net (code "67") (name "Net-(LED1-PadA)") (class "Default")
      (node (ref "LED1") (pin "A") (pinfunction "A_A") (pintype "passive"))
      (node (ref "R2") (pin "1") (pinfunction "1_1") (pintype "passive"))
    )
    (net (code "68") (name "Net-(LED2-PadA)") (class "Default")
      (node (ref "LED2") (pin "A") (pinfunction "A_A") (pintype "passive"))
      (node (ref "R6") (pin "2") (pinfunction "2_2") (pintype "passive"))
    )
    (net (code "69") (name "Net-(LED3-PadA)") (class "Default")
      (node (ref "LED3") (pin "A") (pinfunction "A_A") (pintype "passive"))
      (node (ref "R24") (pin "1") (pinfunction "1_1") (pintype "passive"))
    )
    (net (code "70") (name "Net-(LED4-PadA)") (class "Default")
      (node (ref "LED4") (pin "A") (pinfunction "A_A") (pintype "passive"))
      (node (ref "R22") (pin "1") (pinfunction "1_1") (pintype "passive"))
    )
    (net (code "71") (name "Net-(LED5-PadA)") (class "Default")
      (node (ref "LED5") (pin "A") (pinfunction "A_A") (pintype "passive"))
      (node (ref "R23") (pin "2") (pinfunction "2_2") (pintype "passive"))
    )
    (net (code "72") (name "unconnected-(IC4A-CLKOUT-Pad3)") (class "Default")
      (node (ref "IC4") (pin "3") (pinfunction "CLKOUT_3") (pintype "output"))
    )
    (net (code "73") (name "unconnected-(J2-Pad2)") (class "Default")
      (node (ref "J2") (pin "2") (pinfunction "2_2") (pintype "passive"))
    )
    (net (code "74") (name "unconnected-(J3-Pad5)") (class "Default")
      (node (ref "J3") (pin "5") (pinfunction "5_5") (pintype "passive"))
    )
  )
)
